# preamp_-_copia.net
KiCad netlist of a schematic drawn in Altium Designer
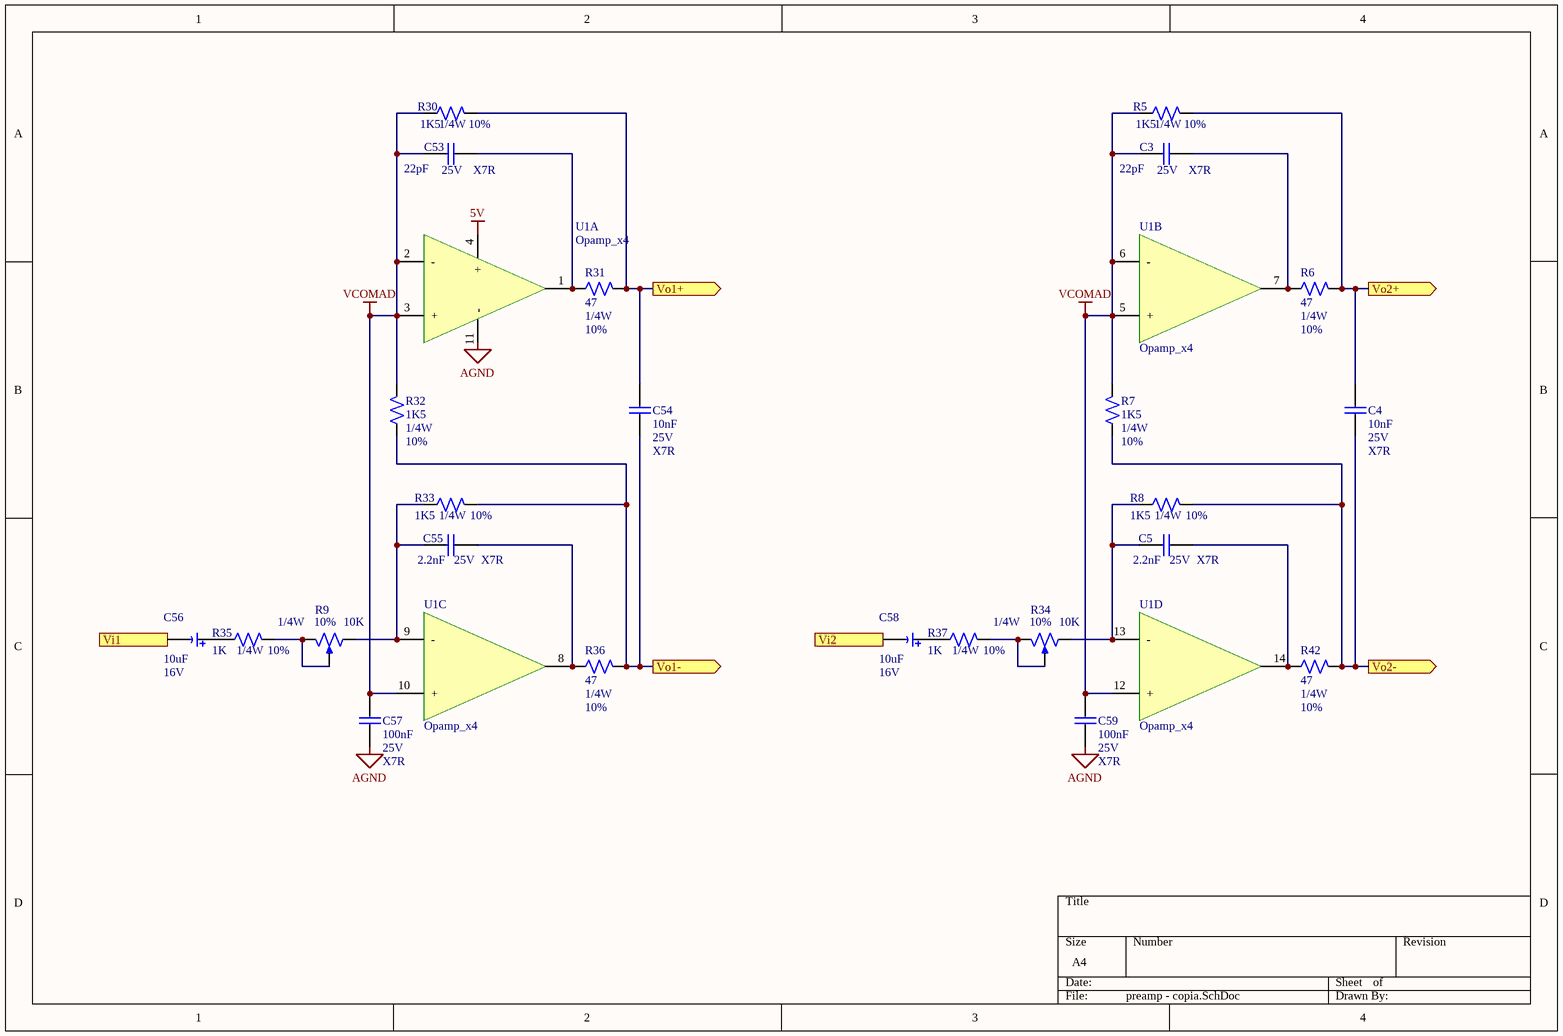
[diagram p0: preamp - copia.SchDoc]

(export (version "E")
  (design (tool "Eeschema 10.0.6"))
  (components
    (comp (ref "C3")
      (value "Capacitor")
      (footprint "C0805")
      (description "Capacitor de placas paralelas")
      (fields (field (name "VALOR") "22pF") (field (name "TENSION") "25V") (field (name "TOLERANCIA") "X7R"))
      (libsource (lib "sch_comunes") (part "Capacitor"))
    )
    (comp (ref "C4")
      (value "Capacitor")
      (footprint "C0805")
      (description "Capacitor de placas paralelas")
      (fields (field (name "VALOR") "10nF") (field (name "TENSION") "25V") (field (name "TOLERANCIA") "X7R"))
      (libsource (lib "sch_comunes") (part "Capacitor"))
    )
    (comp (ref "C5")
      (value "Capacitor")
      (footprint "C0805")
      (description "Capacitor de placas paralelas")
      (fields (field (name "VALOR") "2.2nF") (field (name "TENSION") "25V") (field (name "TOLERANCIA") "X7R"))
      (libsource (lib "sch_comunes") (part "Capacitor"))
    )
    (comp (ref "C53")
      (value "Capacitor")
      (footprint "C0805")
      (description "Capacitor de placas paralelas")
      (fields (field (name "VALOR") "22pF") (field (name "TENSION") "25V") (field (name "TOLERANCIA") "X7R"))
      (libsource (lib "sch_comunes") (part "Capacitor"))
    )
    (comp (ref "C54")
      (value "Capacitor")
      (footprint "C0805")
      (description "Capacitor de placas paralelas")
      (fields (field (name "VALOR") "10nF") (field (name "TENSION") "25V") (field (name "TOLERANCIA") "X7R"))
      (libsource (lib "sch_comunes") (part "Capacitor"))
    )
    (comp (ref "C55")
      (value "Capacitor")
      (footprint "C0805")
      (description "Capacitor de placas paralelas")
      (fields (field (name "VALOR") "2.2nF") (field (name "TENSION") "25V") (field (name "TOLERANCIA") "X7R"))
      (libsource (lib "sch_comunes") (part "Capacitor"))
    )
    (comp (ref "C56")
      (value "Capacitor polarizado")
      (footprint "AVX_C")
      (fields (field (name "VALOR") "10uF") (field (name "TENSION") "16V"))
      (libsource (lib "sch_comunes") (part "Capacitor polarizado"))
    )
    (comp (ref "C57")
      (value "Capacitor")
      (footprint "C0805")
      (description "Capacitor de placas paralelas")
      (fields (field (name "VALOR") "100nF") (field (name "TENSION") "25V") (field (name "TOLERANCIA") "X7R"))
      (libsource (lib "sch_comunes") (part "Capacitor"))
    )
    (comp (ref "C58")
      (value "Capacitor polarizado")
      (footprint "AVX_C")
      (fields (field (name "VALOR") "10uF") (field (name "TENSION") "16V"))
      (libsource (lib "sch_comunes") (part "Capacitor polarizado"))
    )
    (comp (ref "C59")
      (value "Capacitor")
      (footprint "C0805")
      (description "Capacitor de placas paralelas")
      (fields (field (name "VALOR") "100nF") (field (name "TENSION") "25V") (field (name "TOLERANCIA") "X7R"))
      (libsource (lib "sch_comunes") (part "Capacitor"))
    )
    (comp (ref "R5")
      (value "Resistor")
      (footprint "R0603")
      (description "Resistencia")
      (fields (field (name "VALOR") "1K5") (field (name "POTENCIA") "1/4W") (field (name "TOLERANCIA") "10%"))
      (libsource (lib "sch_comunes") (part "Resistor"))
    )
    (comp (ref "R6")
      (value "Resistor")
      (footprint "R0603")
      (description "Resistencia")
      (fields (field (name "VALOR") "47") (field (name "POTENCIA") "1/4W") (field (name "TOLERANCIA") "10%"))
      (libsource (lib "sch_comunes") (part "Resistor"))
    )
    (comp (ref "R7")
      (value "Resistor")
      (footprint "R0603")
      (description "Resistencia")
      (fields (field (name "VALOR") "1K5") (field (name "POTENCIA") "1/4W") (field (name "TOLERANCIA") "10%"))
      (libsource (lib "sch_comunes") (part "Resistor"))
    )
    (comp (ref "R8")
      (value "Resistor")
      (footprint "R0603")
      (description "Resistencia")
      (fields (field (name "VALOR") "1K5") (field (name "POTENCIA") "1/4W") (field (name "TOLERANCIA") "10%"))
      (libsource (lib "sch_comunes") (part "Resistor"))
    )
    (comp (ref "R9")
      (value "Potenciometro")
      (footprint "POTE")
      (fields (field (name "VALOR") "10K") (field (name "TOLERANCIA") "10%") (field (name "POTENCIA") "1/4W"))
      (libsource (lib "sch_comunes") (part "Potenciometer"))
    )
    (comp (ref "R30")
      (value "Resistor")
      (footprint "R0603")
      (description "Resistencia")
      (fields (field (name "VALOR") "1K5") (field (name "POTENCIA") "1/4W") (field (name "TOLERANCIA") "10%"))
      (libsource (lib "sch_comunes") (part "Resistor"))
    )
    (comp (ref "R31")
      (value "Resistor")
      (footprint "R0603")
      (description "Resistencia")
      (fields (field (name "VALOR") "47") (field (name "POTENCIA") "1/4W") (field (name "TOLERANCIA") "10%"))
      (libsource (lib "sch_comunes") (part "Resistor"))
    )
    (comp (ref "R32")
      (value "Resistor")
      (footprint "R0603")
      (description "Resistencia")
      (fields (field (name "VALOR") "1K5") (field (name "POTENCIA") "1/4W") (field (name "TOLERANCIA") "10%"))
      (libsource (lib "sch_comunes") (part "Resistor"))
    )
    (comp (ref "R33")
      (value "Resistor")
      (footprint "R0603")
      (description "Resistencia")
      (fields (field (name "VALOR") "1K5") (field (name "POTENCIA") "1/4W") (field (name "TOLERANCIA") "10%"))
      (libsource (lib "sch_comunes") (part "Resistor"))
    )
    (comp (ref "R34")
      (value "Potenciometro")
      (footprint "POTE")
      (fields (field (name "VALOR") "10K") (field (name "TOLERANCIA") "10%") (field (name "POTENCIA") "1/4W"))
      (libsource (lib "sch_comunes") (part "Potenciometer"))
    )
    (comp (ref "R35")
      (value "Resistor")
      (footprint "R0603")
      (description "Resistencia")
      (fields (field (name "VALOR") "1K") (field (name "POTENCIA") "1/4W") (field (name "TOLERANCIA") "10%"))
      (libsource (lib "sch_comunes") (part "Resistor"))
    )
    (comp (ref "R36")
      (value "Resistor")
      (footprint "R0603")
      (description "Resistencia")
      (fields (field (name "VALOR") "47") (field (name "POTENCIA") "1/4W") (field (name "TOLERANCIA") "10%"))
      (libsource (lib "sch_comunes") (part "Resistor"))
    )
    (comp (ref "R37")
      (value "Resistor")
      (footprint "R0603")
      (description "Resistencia")
      (fields (field (name "VALOR") "1K") (field (name "POTENCIA") "1/4W") (field (name "TOLERANCIA") "10%"))
      (libsource (lib "sch_comunes") (part "Resistor"))
    )
    (comp (ref "R42")
      (value "Resistor")
      (footprint "R0603")
      (description "Resistencia")
      (fields (field (name "VALOR") "47") (field (name "POTENCIA") "1/4W") (field (name "TOLERANCIA") "10%"))
      (libsource (lib "sch_comunes") (part "Resistor"))
    )
    (comp (ref "U1")
      (value "Opamp_x4")
      (footprint "TSSOP-14")
      (description "Integrado con 4 operacionales")
      (libsource (lib "sch_opamp") (part "Opamp_x4"))
    )
  )
  (nets
    (net (code "1") (name "/Vi1") (class "Default")
      (node (ref "C56") (pin "2") (pinfunction "2_2") (pintype "passive"))
    )
    (net (code "2") (name "/Vi2") (class "Default")
      (node (ref "C58") (pin "2") (pinfunction "2_2") (pintype "passive"))
    )
    (net (code "3") (name "/Vo1+") (class "Default")
      (node (ref "C54") (pin "1") (pinfunction "1_1") (pintype "passive"))
      (node (ref "R30") (pin "2") (pinfunction "2_2") (pintype "passive"))
      (node (ref "R31") (pin "2") (pinfunction "2_2") (pintype "passive"))
    )
    (net (code "4") (name "/Vo1-") (class "Default")
      (node (ref "C54") (pin "2") (pinfunction "2_2") (pintype "passive"))
      (node (ref "R32") (pin "1") (pinfunction "1_1") (pintype "passive"))
      (node (ref "R33") (pin "2") (pinfunction "2_2") (pintype "passive"))
      (node (ref "R36") (pin "2") (pinfunction "2_2") (pintype "passive"))
    )
    (net (code "5") (name "/Vo2+") (class "Default")
      (node (ref "C4") (pin "1") (pinfunction "1_1") (pintype "passive"))
      (node (ref "R5") (pin "2") (pinfunction "2_2") (pintype "passive"))
      (node (ref "R6") (pin "2") (pinfunction "2_2") (pintype "passive"))
    )
    (net (code "6") (name "/Vo2-") (class "Default")
      (node (ref "C4") (pin "2") (pinfunction "2_2") (pintype "passive"))
      (node (ref "R42") (pin "2") (pinfunction "2_2") (pintype "passive"))
      (node (ref "R7") (pin "1") (pinfunction "1_1") (pintype "passive"))
      (node (ref "R8") (pin "2") (pinfunction "2_2") (pintype "passive"))
    )
    (net (code "7") (name "5V") (class "Default")
      (node (ref "U1") (pin "4") (pinfunction "+_4") (pintype "power_in"))
    )
    (net (code "8") (name "AGND") (class "Default")
      (node (ref "C57") (pin "2") (pinfunction "2_2") (pintype "passive"))
      (node (ref "C59") (pin "2") (pinfunction "2_2") (pintype "passive"))
      (node (ref "U1") (pin "11") (pinfunction "-_11") (pintype "passive"))
    )
    (net (code "9") (name "Net-(C56-Pad1)") (class "Default")
      (node (ref "C56") (pin "1") (pinfunction "1_1") (pintype "passive"))
      (node (ref "R35") (pin "1") (pinfunction "1_1") (pintype "passive"))
    )
    (net (code "10") (name "Net-(C58-Pad1)") (class "Default")
      (node (ref "C58") (pin "1") (pinfunction "1_1") (pintype "passive"))
      (node (ref "R37") (pin "1") (pinfunction "1_1") (pintype "passive"))
    )
    (net (code "11") (name "Net-(R34-Pad1)") (class "Default")
      (node (ref "R34") (pin "1") (pinfunction "1_1") (pintype "passive"))
      (node (ref "R34") (pin "3") (pinfunction "3_3") (pintype "passive"))
      (node (ref "R37") (pin "2") (pinfunction "2_2") (pintype "passive"))
    )
    (net (code "12") (name "Net-(R35-Pad2)") (class "Default")
      (node (ref "R35") (pin "2") (pinfunction "2_2") (pintype "passive"))
      (node (ref "R9") (pin "1") (pinfunction "1_1") (pintype "passive"))
      (node (ref "R9") (pin "3") (pinfunction "3_3") (pintype "passive"))
    )
    (net (code "13") (name "Net-(U1A-OUT)") (class "Default")
      (node (ref "C53") (pin "1") (pinfunction "1_1") (pintype "passive"))
      (node (ref "R31") (pin "1") (pinfunction "1_1") (pintype "passive"))
      (node (ref "U1") (pin "1") (pinfunction "OUT_1") (pintype "passive"))
    )
    (net (code "14") (name "Net-(U1B-OUT)") (class "Default")
      (node (ref "C3") (pin "1") (pinfunction "1_1") (pintype "passive"))
      (node (ref "R6") (pin "1") (pinfunction "1_1") (pintype "passive"))
      (node (ref "U1") (pin "7") (pinfunction "OUT_7") (pintype "passive"))
    )
    (net (code "15") (name "Net-(U1C--)") (class "Default")
      (node (ref "C55") (pin "2") (pinfunction "2_2") (pintype "passive"))
      (node (ref "R33") (pin "1") (pinfunction "1_1") (pintype "passive"))
      (node (ref "R9") (pin "2") (pinfunction "2_2") (pintype "passive"))
      (node (ref "U1") (pin "9") (pinfunction "-_9") (pintype "passive"))
    )
    (net (code "16") (name "Net-(U1C-OUT)") (class "Default")
      (node (ref "C55") (pin "1") (pinfunction "1_1") (pintype "passive"))
      (node (ref "R36") (pin "1") (pinfunction "1_1") (pintype "passive"))
      (node (ref "U1") (pin "8") (pinfunction "OUT_8") (pintype "passive"))
    )
    (net (code "17") (name "Net-(U1D--)") (class "Default")
      (node (ref "C5") (pin "2") (pinfunction "2_2") (pintype "passive"))
      (node (ref "R34") (pin "2") (pinfunction "2_2") (pintype "passive"))
      (node (ref "R8") (pin "1") (pinfunction "1_1") (pintype "passive"))
      (node (ref "U1") (pin "13") (pinfunction "-_13") (pintype "passive"))
    )
    (net (code "18") (name "Net-(U1D-OUT)") (class "Default")
      (node (ref "C5") (pin "1") (pinfunction "1_1") (pintype "passive"))
      (node (ref "R42") (pin "1") (pinfunction "1_1") (pintype "passive"))
      (node (ref "U1") (pin "14") (pinfunction "OUT_14") (pintype "passive"))
    )
    (net (code "19") (name "VCOMAD") (class "Default")
      (node (ref "C3") (pin "2") (pinfunction "2_2") (pintype "passive"))
      (node (ref "C53") (pin "2") (pinfunction "2_2") (pintype "passive"))
      (node (ref "C57") (pin "1") (pinfunction "1_1") (pintype "passive"))
      (node (ref "C59") (pin "1") (pinfunction "1_1") (pintype "passive"))
      (node (ref "R30") (pin "1") (pinfunction "1_1") (pintype "passive"))
      (node (ref "R32") (pin "2") (pinfunction "2_2") (pintype "passive"))
      (node (ref "R5") (pin "1") (pinfunction "1_1") (pintype "passive"))
      (node (ref "R7") (pin "2") (pinfunction "2_2") (pintype "passive"))
      (node (ref "U1") (pin "10") (pinfunction "+_10") (pintype "passive"))
      (node (ref "U1") (pin "12") (pinfunction "+_12") (pintype "passive"))
      (node (ref "U1") (pin "2") (pinfunction "-_2") (pintype "passive"))
      (node (ref "U1") (pin "3") (pinfunction "+_3") (pintype "passive"))
      (node (ref "U1") (pin "5") (pinfunction "+_5") (pintype "passive"))
      (node (ref "U1") (pin "6") (pinfunction "-_6") (pintype "passive"))
    )
  )
)
